# breakout_022218.net
KiCad netlist of a schematic drawn in EAGLE
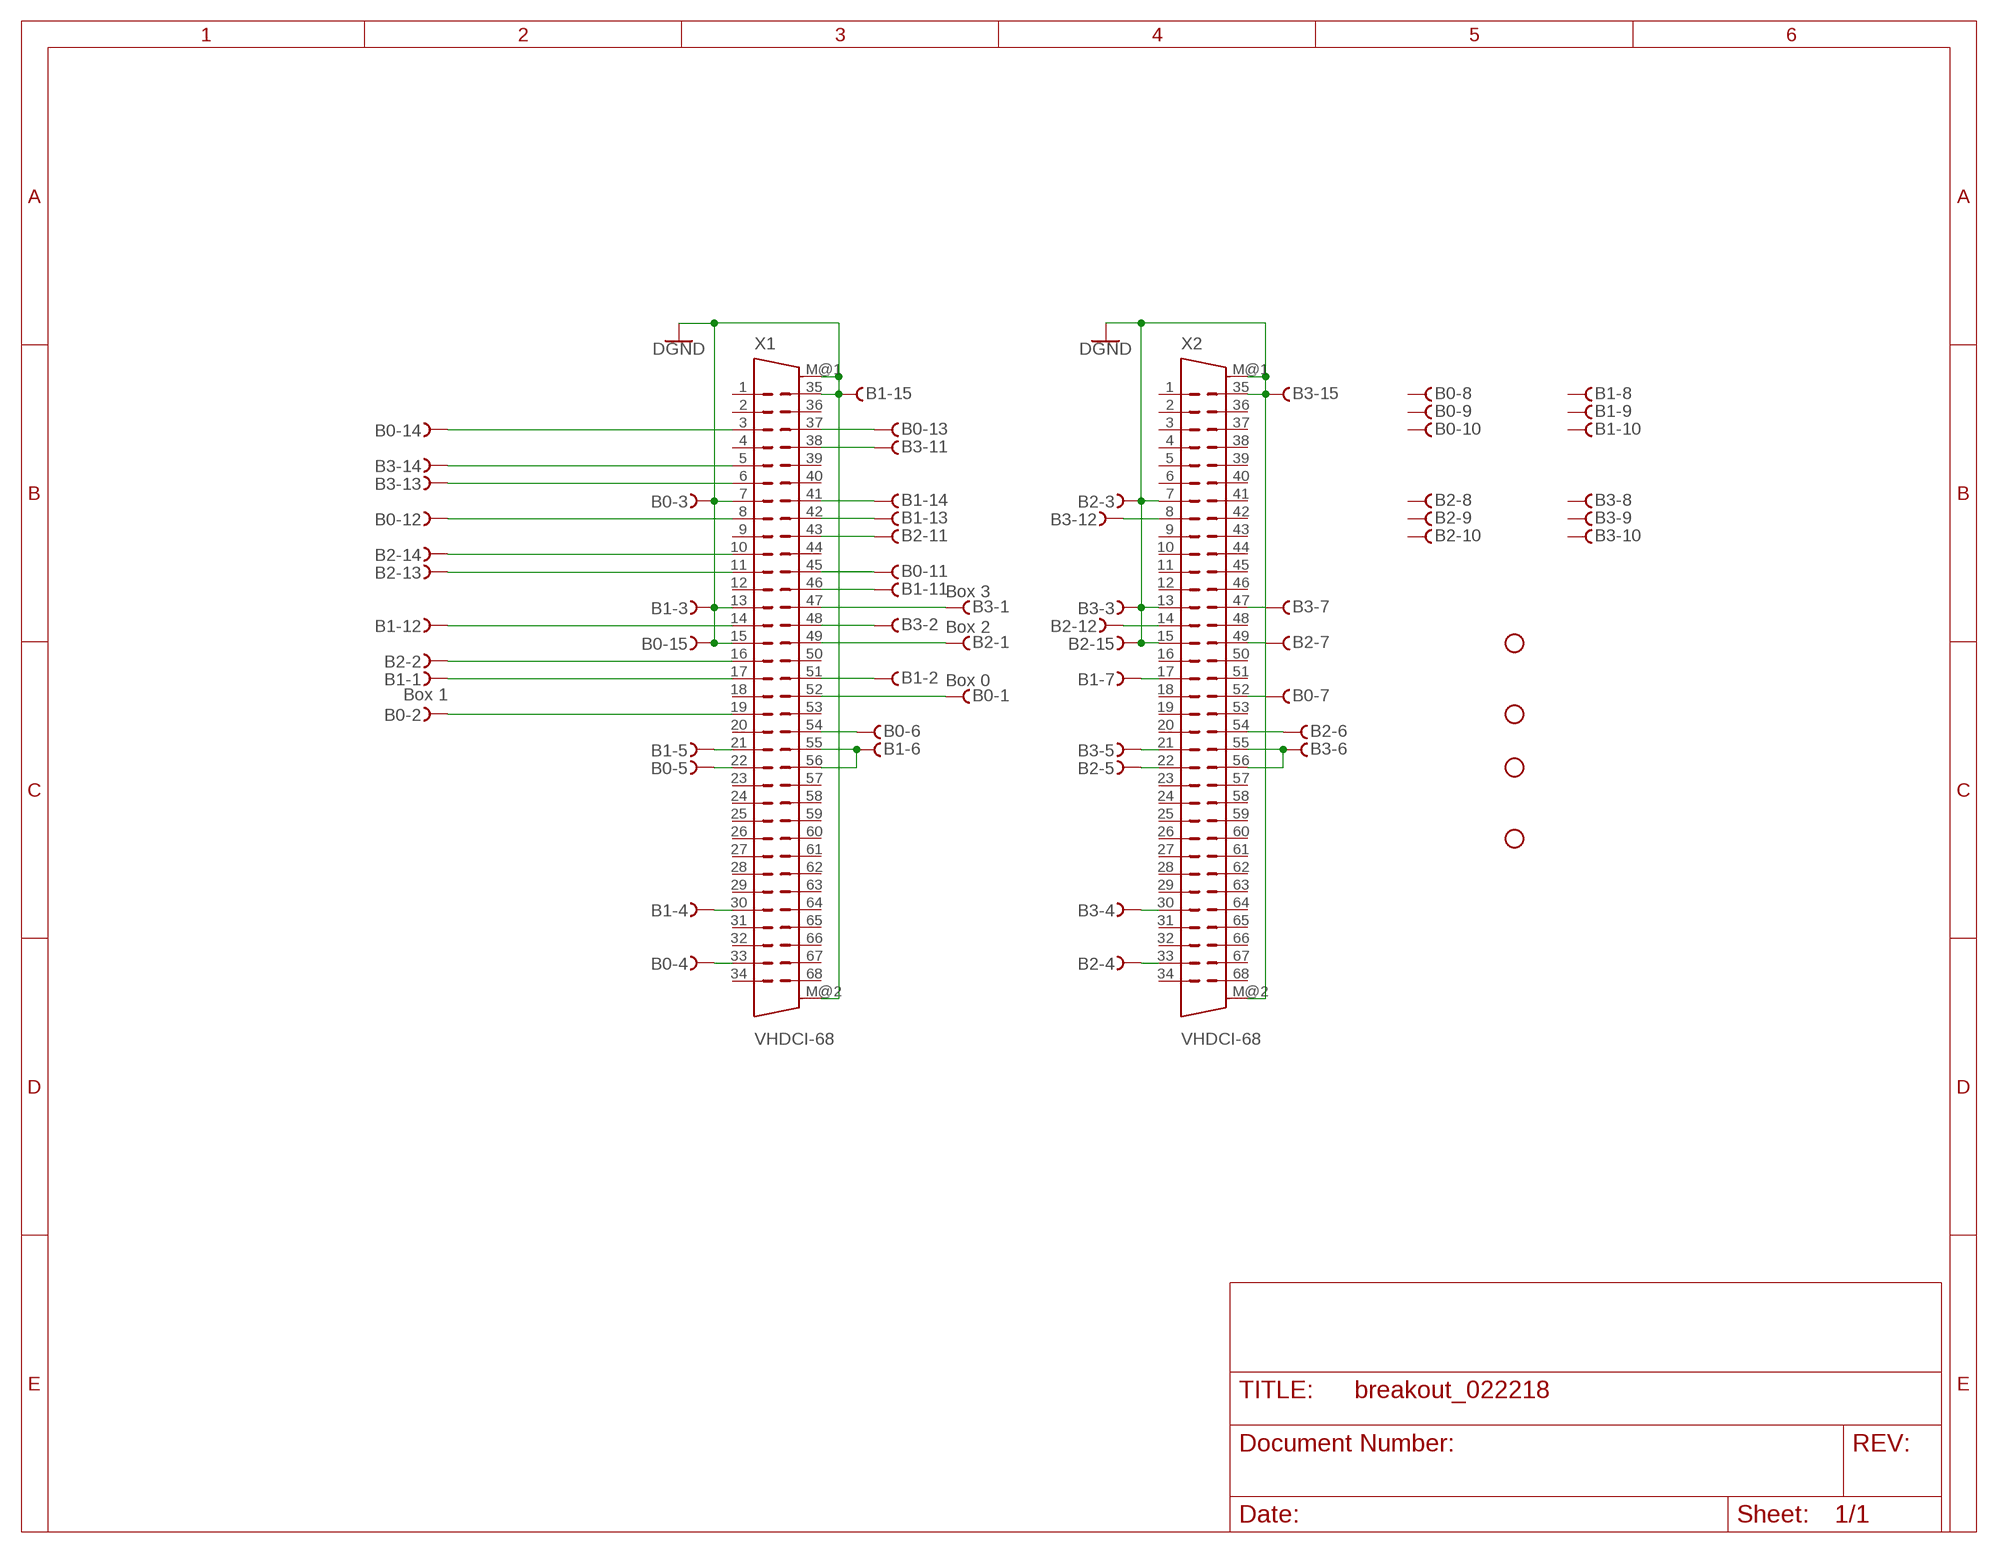
[diagram p0: schematic, sheet 1]

(export (version "E")
  (design (tool "Eeschema 10.0.6"))
  (components
    (comp (ref "B0")
      (value "Box 0")
      (footprint "eagle-import:HDR15RA")
      (libsource (lib "eagle-import") (part "D-SUB15-HDR15RA"))
    )
    (comp (ref "B1")
      (value "Box 1")
      (footprint "eagle-import:HDR15RA")
      (libsource (lib "eagle-import") (part "D-SUB15-HDR15RA"))
    )
    (comp (ref "B2")
      (value "Box 2")
      (footprint "eagle-import:HDR15RA")
      (libsource (lib "eagle-import") (part "D-SUB15-HDR15RA"))
    )
    (comp (ref "B3")
      (value "Box 3")
      (footprint "eagle-import:HDR15RA")
      (libsource (lib "eagle-import") (part "D-SUB15-HDR15RA"))
    )
    (comp (ref "H1")
      (value "STAND-OFF")
      (footprint "eagle-import:STAND-OFF")
      (libsource (lib "eagle-import") (part "STAND-OFF"))
    )
    (comp (ref "H2")
      (value "STAND-OFF")
      (footprint "eagle-import:STAND-OFF")
      (libsource (lib "eagle-import") (part "STAND-OFF"))
    )
    (comp (ref "H3")
      (value "STAND-OFF")
      (footprint "eagle-import:STAND-OFF")
      (libsource (lib "eagle-import") (part "STAND-OFF"))
    )
    (comp (ref "H4")
      (value "STAND-OFF")
      (footprint "eagle-import:STAND-OFF")
      (libsource (lib "eagle-import") (part "STAND-OFF"))
    )
    (comp (ref "X1")
      (value "VHDCI-68")
      (footprint "eagle-import:VHDCI-68")
      (fields (field (name "MF") "MOLEX"))
      (libsource (lib "eagle-import") (part "VHDCI-68"))
    )
    (comp (ref "X2")
      (value "VHDCI-68")
      (footprint "eagle-import:VHDCI-68")
      (fields (field (name "MF") "MOLEX"))
      (libsource (lib "eagle-import") (part "VHDCI-68"))
    )
  )
  (nets
    (net (code "1") (name "DGND") (class "Default")
      (node (ref "B0") (pin "15") (pinfunction "F_15") (pintype "passive"))
      (node (ref "B0") (pin "3") (pinfunction "F_3") (pintype "passive"))
      (node (ref "B1") (pin "15") (pinfunction "F_15") (pintype "passive"))
      (node (ref "B1") (pin "3") (pinfunction "F_3") (pintype "passive"))
      (node (ref "B2") (pin "15") (pinfunction "F_15") (pintype "passive"))
      (node (ref "B2") (pin "3") (pinfunction "F_3") (pintype "passive"))
      (node (ref "B3") (pin "15") (pinfunction "F_15") (pintype "passive"))
      (node (ref "B3") (pin "3") (pinfunction "F_3") (pintype "passive"))
      (node (ref "X1") (pin "13") (pinfunction "13_13") (pintype "passive"))
      (node (ref "X1") (pin "15") (pinfunction "15_15") (pintype "passive"))
      (node (ref "X1") (pin "35") (pinfunction "35_35") (pintype "passive"))
      (node (ref "X1") (pin "7") (pinfunction "7_7") (pintype "passive"))
      (node (ref "X1") (pin "M@1") (pinfunction "S_M@1") (pintype "passive"))
      (node (ref "X1") (pin "M@2") (pinfunction "S_M@2") (pintype "passive"))
      (node (ref "X2") (pin "13") (pinfunction "13_13") (pintype "passive"))
      (node (ref "X2") (pin "15") (pinfunction "15_15") (pintype "passive"))
      (node (ref "X2") (pin "35") (pinfunction "35_35") (pintype "passive"))
      (node (ref "X2") (pin "7") (pinfunction "7_7") (pintype "passive"))
      (node (ref "X2") (pin "M@1") (pinfunction "S_M@1") (pintype "passive"))
      (node (ref "X2") (pin "M@2") (pinfunction "S_M@2") (pintype "passive"))
    )
    (net (code "2") (name "Net-(B0A-F)") (class "Default")
      (node (ref "B0") (pin "1") (pinfunction "F_1") (pintype "passive"))
      (node (ref "X1") (pin "52") (pinfunction "52_52") (pintype "passive"))
    )
    (net (code "3") (name "Net-(B0C-F)") (class "Default")
      (node (ref "B0") (pin "11") (pinfunction "F_11") (pintype "passive"))
      (node (ref "X1") (pin "45") (pinfunction "45_45") (pintype "passive"))
    )
    (net (code "4") (name "Net-(B0D-F)") (class "Default")
      (node (ref "B0") (pin "12") (pinfunction "F_12") (pintype "passive"))
      (node (ref "X1") (pin "8") (pinfunction "8_8") (pintype "passive"))
    )
    (net (code "5") (name "Net-(B0E-F)") (class "Default")
      (node (ref "B0") (pin "13") (pinfunction "F_13") (pintype "passive"))
      (node (ref "X1") (pin "37") (pinfunction "37_37") (pintype "passive"))
    )
    (net (code "6") (name "Net-(B0F-F)") (class "Default")
      (node (ref "B0") (pin "14") (pinfunction "F_14") (pintype "passive"))
      (node (ref "X1") (pin "3") (pinfunction "3_3") (pintype "passive"))
    )
    (net (code "7") (name "Net-(B0H-F)") (class "Default")
      (node (ref "B0") (pin "2") (pinfunction "F_2") (pintype "passive"))
      (node (ref "X1") (pin "19") (pinfunction "19_19") (pintype "passive"))
    )
    (net (code "8") (name "Net-(B0J-F)") (class "Default")
      (node (ref "B0") (pin "4") (pinfunction "F_4") (pintype "passive"))
      (node (ref "X1") (pin "33") (pinfunction "33_33") (pintype "passive"))
    )
    (net (code "9") (name "Net-(B0K-F)") (class "Default")
      (node (ref "B0") (pin "5") (pinfunction "F_5") (pintype "passive"))
      (node (ref "X1") (pin "22") (pinfunction "22_22") (pintype "passive"))
    )
    (net (code "10") (name "Net-(B0L-F)") (class "Default")
      (node (ref "B0") (pin "6") (pinfunction "F_6") (pintype "passive"))
      (node (ref "X1") (pin "54") (pinfunction "54_54") (pintype "passive"))
    )
    (net (code "11") (name "Net-(B0M-F)") (class "Default")
      (node (ref "B0") (pin "7") (pinfunction "F_7") (pintype "passive"))
      (node (ref "X2") (pin "52") (pinfunction "52_52") (pintype "passive"))
    )
    (net (code "12") (name "Net-(B1A-F)") (class "Default")
      (node (ref "B1") (pin "1") (pinfunction "F_1") (pintype "passive"))
      (node (ref "X1") (pin "17") (pinfunction "17_17") (pintype "passive"))
    )
    (net (code "13") (name "Net-(B1C-F)") (class "Default")
      (node (ref "B1") (pin "11") (pinfunction "F_11") (pintype "passive"))
      (node (ref "X1") (pin "46") (pinfunction "46_46") (pintype "passive"))
    )
    (net (code "14") (name "Net-(B1D-F)") (class "Default")
      (node (ref "B1") (pin "12") (pinfunction "F_12") (pintype "passive"))
      (node (ref "X1") (pin "14") (pinfunction "14_14") (pintype "passive"))
    )
    (net (code "15") (name "Net-(B1E-F)") (class "Default")
      (node (ref "B1") (pin "13") (pinfunction "F_13") (pintype "passive"))
      (node (ref "X1") (pin "42") (pinfunction "42_42") (pintype "passive"))
    )
    (net (code "16") (name "Net-(B1F-F)") (class "Default")
      (node (ref "B1") (pin "14") (pinfunction "F_14") (pintype "passive"))
      (node (ref "X1") (pin "41") (pinfunction "41_41") (pintype "passive"))
    )
    (net (code "17") (name "Net-(B1H-F)") (class "Default")
      (node (ref "B1") (pin "2") (pinfunction "F_2") (pintype "passive"))
      (node (ref "X1") (pin "51") (pinfunction "51_51") (pintype "passive"))
    )
    (net (code "18") (name "Net-(B1J-F)") (class "Default")
      (node (ref "B1") (pin "4") (pinfunction "F_4") (pintype "passive"))
      (node (ref "X1") (pin "30") (pinfunction "30_30") (pintype "passive"))
    )
    (net (code "19") (name "Net-(B1K-F)") (class "Default")
      (node (ref "B1") (pin "5") (pinfunction "F_5") (pintype "passive"))
      (node (ref "X1") (pin "21") (pinfunction "21_21") (pintype "passive"))
    )
    (net (code "20") (name "Net-(B1L-F)") (class "Default")
      (node (ref "B1") (pin "6") (pinfunction "F_6") (pintype "passive"))
      (node (ref "X1") (pin "55") (pinfunction "55_55") (pintype "passive"))
      (node (ref "X1") (pin "56") (pinfunction "56_56") (pintype "passive"))
    )
    (net (code "21") (name "Net-(B1M-F)") (class "Default")
      (node (ref "B1") (pin "7") (pinfunction "F_7") (pintype "passive"))
      (node (ref "X2") (pin "17") (pinfunction "17_17") (pintype "passive"))
    )
    (net (code "22") (name "Net-(B2A-F)") (class "Default")
      (node (ref "B2") (pin "1") (pinfunction "F_1") (pintype "passive"))
      (node (ref "X1") (pin "49") (pinfunction "49_49") (pintype "passive"))
    )
    (net (code "23") (name "Net-(B2C-F)") (class "Default")
      (node (ref "B2") (pin "11") (pinfunction "F_11") (pintype "passive"))
      (node (ref "X1") (pin "43") (pinfunction "43_43") (pintype "passive"))
    )
    (net (code "24") (name "Net-(B2D-F)") (class "Default")
      (node (ref "B2") (pin "12") (pinfunction "F_12") (pintype "passive"))
      (node (ref "X2") (pin "14") (pinfunction "14_14") (pintype "passive"))
    )
    (net (code "25") (name "Net-(B2E-F)") (class "Default")
      (node (ref "B2") (pin "13") (pinfunction "F_13") (pintype "passive"))
      (node (ref "X1") (pin "11") (pinfunction "11_11") (pintype "passive"))
    )
    (net (code "26") (name "Net-(B2F-F)") (class "Default")
      (node (ref "B2") (pin "14") (pinfunction "F_14") (pintype "passive"))
      (node (ref "X1") (pin "10") (pinfunction "10_10") (pintype "passive"))
    )
    (net (code "27") (name "Net-(B2H-F)") (class "Default")
      (node (ref "B2") (pin "2") (pinfunction "F_2") (pintype "passive"))
      (node (ref "X1") (pin "16") (pinfunction "16_16") (pintype "passive"))
    )
    (net (code "28") (name "Net-(B2J-F)") (class "Default")
      (node (ref "B2") (pin "4") (pinfunction "F_4") (pintype "passive"))
      (node (ref "X2") (pin "33") (pinfunction "33_33") (pintype "passive"))
    )
    (net (code "29") (name "Net-(B2K-F)") (class "Default")
      (node (ref "B2") (pin "5") (pinfunction "F_5") (pintype "passive"))
      (node (ref "X2") (pin "22") (pinfunction "22_22") (pintype "passive"))
    )
    (net (code "30") (name "Net-(B2L-F)") (class "Default")
      (node (ref "B2") (pin "6") (pinfunction "F_6") (pintype "passive"))
      (node (ref "X2") (pin "54") (pinfunction "54_54") (pintype "passive"))
    )
    (net (code "31") (name "Net-(B2M-F)") (class "Default")
      (node (ref "B2") (pin "7") (pinfunction "F_7") (pintype "passive"))
      (node (ref "X2") (pin "49") (pinfunction "49_49") (pintype "passive"))
    )
    (net (code "32") (name "Net-(B3A-F)") (class "Default")
      (node (ref "B3") (pin "1") (pinfunction "F_1") (pintype "passive"))
      (node (ref "X1") (pin "47") (pinfunction "47_47") (pintype "passive"))
    )
    (net (code "33") (name "Net-(B3C-F)") (class "Default")
      (node (ref "B3") (pin "11") (pinfunction "F_11") (pintype "passive"))
      (node (ref "X1") (pin "38") (pinfunction "38_38") (pintype "passive"))
    )
    (net (code "34") (name "Net-(B3D-F)") (class "Default")
      (node (ref "B3") (pin "12") (pinfunction "F_12") (pintype "passive"))
      (node (ref "X2") (pin "8") (pinfunction "8_8") (pintype "passive"))
    )
    (net (code "35") (name "Net-(B3E-F)") (class "Default")
      (node (ref "B3") (pin "13") (pinfunction "F_13") (pintype "passive"))
      (node (ref "X1") (pin "6") (pinfunction "6_6") (pintype "passive"))
    )
    (net (code "36") (name "Net-(B3F-F)") (class "Default")
      (node (ref "B3") (pin "14") (pinfunction "F_14") (pintype "passive"))
      (node (ref "X1") (pin "5") (pinfunction "5_5") (pintype "passive"))
    )
    (net (code "37") (name "Net-(B3H-F)") (class "Default")
      (node (ref "B3") (pin "2") (pinfunction "F_2") (pintype "passive"))
      (node (ref "X1") (pin "48") (pinfunction "48_48") (pintype "passive"))
    )
    (net (code "38") (name "Net-(B3J-F)") (class "Default")
      (node (ref "B3") (pin "4") (pinfunction "F_4") (pintype "passive"))
      (node (ref "X2") (pin "30") (pinfunction "30_30") (pintype "passive"))
    )
    (net (code "39") (name "Net-(B3K-F)") (class "Default")
      (node (ref "B3") (pin "5") (pinfunction "F_5") (pintype "passive"))
      (node (ref "X2") (pin "21") (pinfunction "21_21") (pintype "passive"))
    )
    (net (code "40") (name "Net-(B3L-F)") (class "Default")
      (node (ref "B3") (pin "6") (pinfunction "F_6") (pintype "passive"))
      (node (ref "X2") (pin "55") (pinfunction "55_55") (pintype "passive"))
      (node (ref "X2") (pin "56") (pinfunction "56_56") (pintype "passive"))
    )
    (net (code "41") (name "Net-(B3M-F)") (class "Default")
      (node (ref "B3") (pin "7") (pinfunction "F_7") (pintype "passive"))
      (node (ref "X2") (pin "47") (pinfunction "47_47") (pintype "passive"))
    )
    (net (code "42") (name "unconnected-(B0B-F-Pad10)") (class "Default")
      (node (ref "B0") (pin "10") (pinfunction "F_10") (pintype "passive"))
    )
    (net (code "43") (name "unconnected-(B0N-F-Pad8)") (class "Default")
      (node (ref "B0") (pin "8") (pinfunction "F_8") (pintype "passive"))
    )
    (net (code "44") (name "unconnected-(B0O-F-Pad9)") (class "Default")
      (node (ref "B0") (pin "9") (pinfunction "F_9") (pintype "passive"))
    )
    (net (code "45") (name "unconnected-(B1B-F-Pad10)") (class "Default")
      (node (ref "B1") (pin "10") (pinfunction "F_10") (pintype "passive"))
    )
    (net (code "46") (name "unconnected-(B1N-F-Pad8)") (class "Default")
      (node (ref "B1") (pin "8") (pinfunction "F_8") (pintype "passive"))
    )
    (net (code "47") (name "unconnected-(B1O-F-Pad9)") (class "Default")
      (node (ref "B1") (pin "9") (pinfunction "F_9") (pintype "passive"))
    )
    (net (code "48") (name "unconnected-(B2B-F-Pad10)") (class "Default")
      (node (ref "B2") (pin "10") (pinfunction "F_10") (pintype "passive"))
    )
    (net (code "49") (name "unconnected-(B2N-F-Pad8)") (class "Default")
      (node (ref "B2") (pin "8") (pinfunction "F_8") (pintype "passive"))
    )
    (net (code "50") (name "unconnected-(B2O-F-Pad9)") (class "Default")
      (node (ref "B2") (pin "9") (pinfunction "F_9") (pintype "passive"))
    )
    (net (code "51") (name "unconnected-(B3B-F-Pad10)") (class "Default")
      (node (ref "B3") (pin "10") (pinfunction "F_10") (pintype "passive"))
    )
    (net (code "52") (name "unconnected-(B3N-F-Pad8)") (class "Default")
      (node (ref "B3") (pin "8") (pinfunction "F_8") (pintype "passive"))
    )
    (net (code "53") (name "unconnected-(B3O-F-Pad9)") (class "Default")
      (node (ref "B3") (pin "9") (pinfunction "F_9") (pintype "passive"))
    )
    (net (code "54") (name "unconnected-(X1-Pad1)") (class "Default")
      (node (ref "X1") (pin "1") (pinfunction "1_1") (pintype "passive"))
    )
    (net (code "55") (name "unconnected-(X1-Pad2)") (class "Default")
      (node (ref "X1") (pin "2") (pinfunction "2_2") (pintype "passive"))
    )
    (net (code "56") (name "unconnected-(X1-Pad4)") (class "Default")
      (node (ref "X1") (pin "4") (pinfunction "4_4") (pintype "passive"))
    )
    (net (code "57") (name "unconnected-(X1-Pad9)") (class "Default")
      (node (ref "X1") (pin "9") (pinfunction "9_9") (pintype "passive"))
    )
    (net (code "58") (name "unconnected-(X1-Pad12)") (class "Default")
      (node (ref "X1") (pin "12") (pinfunction "12_12") (pintype "passive"))
    )
    (net (code "59") (name "unconnected-(X1-Pad18)") (class "Default")
      (node (ref "X1") (pin "18") (pinfunction "18_18") (pintype "passive"))
    )
    (net (code "60") (name "unconnected-(X1-Pad20)") (class "Default")
      (node (ref "X1") (pin "20") (pinfunction "20_20") (pintype "passive"))
    )
    (net (code "61") (name "unconnected-(X1-Pad23)") (class "Default")
      (node (ref "X1") (pin "23") (pinfunction "23_23") (pintype "passive"))
    )
    (net (code "62") (name "unconnected-(X1-Pad24)") (class "Default")
      (node (ref "X1") (pin "24") (pinfunction "24_24") (pintype "passive"))
    )
    (net (code "63") (name "unconnected-(X1-Pad25)") (class "Default")
      (node (ref "X1") (pin "25") (pinfunction "25_25") (pintype "passive"))
    )
    (net (code "64") (name "unconnected-(X1-Pad26)") (class "Default")
      (node (ref "X1") (pin "26") (pinfunction "26_26") (pintype "passive"))
    )
    (net (code "65") (name "unconnected-(X1-Pad27)") (class "Default")
      (node (ref "X1") (pin "27") (pinfunction "27_27") (pintype "passive"))
    )
    (net (code "66") (name "unconnected-(X1-Pad28)") (class "Default")
      (node (ref "X1") (pin "28") (pinfunction "28_28") (pintype "passive"))
    )
    (net (code "67") (name "unconnected-(X1-Pad29)") (class "Default")
      (node (ref "X1") (pin "29") (pinfunction "29_29") (pintype "passive"))
    )
    (net (code "68") (name "unconnected-(X1-Pad31)") (class "Default")
      (node (ref "X1") (pin "31") (pinfunction "31_31") (pintype "passive"))
    )
    (net (code "69") (name "unconnected-(X1-Pad32)") (class "Default")
      (node (ref "X1") (pin "32") (pinfunction "32_32") (pintype "passive"))
    )
    (net (code "70") (name "unconnected-(X1-Pad34)") (class "Default")
      (node (ref "X1") (pin "34") (pinfunction "34_34") (pintype "passive"))
    )
    (net (code "71") (name "unconnected-(X1-Pad36)") (class "Default")
      (node (ref "X1") (pin "36") (pinfunction "36_36") (pintype "passive"))
    )
    (net (code "72") (name "unconnected-(X1-Pad39)") (class "Default")
      (node (ref "X1") (pin "39") (pinfunction "39_39") (pintype "passive"))
    )
    (net (code "73") (name "unconnected-(X1-Pad40)") (class "Default")
      (node (ref "X1") (pin "40") (pinfunction "40_40") (pintype "passive"))
    )
    (net (code "74") (name "unconnected-(X1-Pad44)") (class "Default")
      (node (ref "X1") (pin "44") (pinfunction "44_44") (pintype "passive"))
    )
    (net (code "75") (name "unconnected-(X1-Pad50)") (class "Default")
      (node (ref "X1") (pin "50") (pinfunction "50_50") (pintype "passive"))
    )
    (net (code "76") (name "unconnected-(X1-Pad53)") (class "Default")
      (node (ref "X1") (pin "53") (pinfunction "53_53") (pintype "passive"))
    )
    (net (code "77") (name "unconnected-(X1-Pad57)") (class "Default")
      (node (ref "X1") (pin "57") (pinfunction "57_57") (pintype "passive"))
    )
    (net (code "78") (name "unconnected-(X1-Pad58)") (class "Default")
      (node (ref "X1") (pin "58") (pinfunction "58_58") (pintype "passive"))
    )
    (net (code "79") (name "unconnected-(X1-Pad59)") (class "Default")
      (node (ref "X1") (pin "59") (pinfunction "59_59") (pintype "passive"))
    )
    (net (code "80") (name "unconnected-(X1-Pad60)") (class "Default")
      (node (ref "X1") (pin "60") (pinfunction "60_60") (pintype "passive"))
    )
    (net (code "81") (name "unconnected-(X1-Pad61)") (class "Default")
      (node (ref "X1") (pin "61") (pinfunction "61_61") (pintype "passive"))
    )
    (net (code "82") (name "unconnected-(X1-Pad62)") (class "Default")
      (node (ref "X1") (pin "62") (pinfunction "62_62") (pintype "passive"))
    )
    (net (code "83") (name "unconnected-(X1-Pad63)") (class "Default")
      (node (ref "X1") (pin "63") (pinfunction "63_63") (pintype "passive"))
    )
    (net (code "84") (name "unconnected-(X1-Pad64)") (class "Default")
      (node (ref "X1") (pin "64") (pinfunction "64_64") (pintype "passive"))
    )
    (net (code "85") (name "unconnected-(X1-Pad65)") (class "Default")
      (node (ref "X1") (pin "65") (pinfunction "65_65") (pintype "passive"))
    )
    (net (code "86") (name "unconnected-(X1-Pad66)") (class "Default")
      (node (ref "X1") (pin "66") (pinfunction "66_66") (pintype "passive"))
    )
    (net (code "87") (name "unconnected-(X1-Pad67)") (class "Default")
      (node (ref "X1") (pin "67") (pinfunction "67_67") (pintype "passive"))
    )
    (net (code "88") (name "unconnected-(X1-Pad68)") (class "Default")
      (node (ref "X1") (pin "68") (pinfunction "68_68") (pintype "passive"))
    )
    (net (code "89") (name "unconnected-(X2-Pad1)") (class "Default")
      (node (ref "X2") (pin "1") (pinfunction "1_1") (pintype "passive"))
    )
    (net (code "90") (name "unconnected-(X2-Pad2)") (class "Default")
      (node (ref "X2") (pin "2") (pinfunction "2_2") (pintype "passive"))
    )
    (net (code "91") (name "unconnected-(X2-Pad3)") (class "Default")
      (node (ref "X2") (pin "3") (pinfunction "3_3") (pintype "passive"))
    )
    (net (code "92") (name "unconnected-(X2-Pad4)") (class "Default")
      (node (ref "X2") (pin "4") (pinfunction "4_4") (pintype "passive"))
    )
    (net (code "93") (name "unconnected-(X2-Pad5)") (class "Default")
      (node (ref "X2") (pin "5") (pinfunction "5_5") (pintype "passive"))
    )
    (net (code "94") (name "unconnected-(X2-Pad6)") (class "Default")
      (node (ref "X2") (pin "6") (pinfunction "6_6") (pintype "passive"))
    )
    (net (code "95") (name "unconnected-(X2-Pad9)") (class "Default")
      (node (ref "X2") (pin "9") (pinfunction "9_9") (pintype "passive"))
    )
    (net (code "96") (name "unconnected-(X2-Pad10)") (class "Default")
      (node (ref "X2") (pin "10") (pinfunction "10_10") (pintype "passive"))
    )
    (net (code "97") (name "unconnected-(X2-Pad11)") (class "Default")
      (node (ref "X2") (pin "11") (pinfunction "11_11") (pintype "passive"))
    )
    (net (code "98") (name "unconnected-(X2-Pad12)") (class "Default")
      (node (ref "X2") (pin "12") (pinfunction "12_12") (pintype "passive"))
    )
    (net (code "99") (name "unconnected-(X2-Pad16)") (class "Default")
      (node (ref "X2") (pin "16") (pinfunction "16_16") (pintype "passive"))
    )
    (net (code "100") (name "unconnected-(X2-Pad18)") (class "Default")
      (node (ref "X2") (pin "18") (pinfunction "18_18") (pintype "passive"))
    )
    (net (code "101") (name "unconnected-(X2-Pad19)") (class "Default")
      (node (ref "X2") (pin "19") (pinfunction "19_19") (pintype "passive"))
    )
    (net (code "102") (name "unconnected-(X2-Pad20)") (class "Default")
      (node (ref "X2") (pin "20") (pinfunction "20_20") (pintype "passive"))
    )
    (net (code "103") (name "unconnected-(X2-Pad23)") (class "Default")
      (node (ref "X2") (pin "23") (pinfunction "23_23") (pintype "passive"))
    )
    (net (code "104") (name "unconnected-(X2-Pad24)") (class "Default")
      (node (ref "X2") (pin "24") (pinfunction "24_24") (pintype "passive"))
    )
    (net (code "105") (name "unconnected-(X2-Pad25)") (class "Default")
      (node (ref "X2") (pin "25") (pinfunction "25_25") (pintype "passive"))
    )
    (net (code "106") (name "unconnected-(X2-Pad26)") (class "Default")
      (node (ref "X2") (pin "26") (pinfunction "26_26") (pintype "passive"))
    )
    (net (code "107") (name "unconnected-(X2-Pad27)") (class "Default")
      (node (ref "X2") (pin "27") (pinfunction "27_27") (pintype "passive"))
    )
    (net (code "108") (name "unconnected-(X2-Pad28)") (class "Default")
      (node (ref "X2") (pin "28") (pinfunction "28_28") (pintype "passive"))
    )
    (net (code "109") (name "unconnected-(X2-Pad29)") (class "Default")
      (node (ref "X2") (pin "29") (pinfunction "29_29") (pintype "passive"))
    )
    (net (code "110") (name "unconnected-(X2-Pad31)") (class "Default")
      (node (ref "X2") (pin "31") (pinfunction "31_31") (pintype "passive"))
    )
    (net (code "111") (name "unconnected-(X2-Pad32)") (class "Default")
      (node (ref "X2") (pin "32") (pinfunction "32_32") (pintype "passive"))
    )
    (net (code "112") (name "unconnected-(X2-Pad34)") (class "Default")
      (node (ref "X2") (pin "34") (pinfunction "34_34") (pintype "passive"))
    )
    (net (code "113") (name "unconnected-(X2-Pad36)") (class "Default")
      (node (ref "X2") (pin "36") (pinfunction "36_36") (pintype "passive"))
    )
    (net (code "114") (name "unconnected-(X2-Pad37)") (class "Default")
      (node (ref "X2") (pin "37") (pinfunction "37_37") (pintype "passive"))
    )
    (net (code "115") (name "unconnected-(X2-Pad38)") (class "Default")
      (node (ref "X2") (pin "38") (pinfunction "38_38") (pintype "passive"))
    )
    (net (code "116") (name "unconnected-(X2-Pad39)") (class "Default")
      (node (ref "X2") (pin "39") (pinfunction "39_39") (pintype "passive"))
    )
    (net (code "117") (name "unconnected-(X2-Pad40)") (class "Default")
      (node (ref "X2") (pin "40") (pinfunction "40_40") (pintype "passive"))
    )
    (net (code "118") (name "unconnected-(X2-Pad41)") (class "Default")
      (node (ref "X2") (pin "41") (pinfunction "41_41") (pintype "passive"))
    )
    (net (code "119") (name "unconnected-(X2-Pad42)") (class "Default")
      (node (ref "X2") (pin "42") (pinfunction "42_42") (pintype "passive"))
    )
    (net (code "120") (name "unconnected-(X2-Pad43)") (class "Default")
      (node (ref "X2") (pin "43") (pinfunction "43_43") (pintype "passive"))
    )
    (net (code "121") (name "unconnected-(X2-Pad44)") (class "Default")
      (node (ref "X2") (pin "44") (pinfunction "44_44") (pintype "passive"))
    )
    (net (code "122") (name "unconnected-(X2-Pad45)") (class "Default")
      (node (ref "X2") (pin "45") (pinfunction "45_45") (pintype "passive"))
    )
    (net (code "123") (name "unconnected-(X2-Pad46)") (class "Default")
      (node (ref "X2") (pin "46") (pinfunction "46_46") (pintype "passive"))
    )
    (net (code "124") (name "unconnected-(X2-Pad48)") (class "Default")
      (node (ref "X2") (pin "48") (pinfunction "48_48") (pintype "passive"))
    )
    (net (code "125") (name "unconnected-(X2-Pad50)") (class "Default")
      (node (ref "X2") (pin "50") (pinfunction "50_50") (pintype "passive"))
    )
    (net (code "126") (name "unconnected-(X2-Pad51)") (class "Default")
      (node (ref "X2") (pin "51") (pinfunction "51_51") (pintype "passive"))
    )
    (net (code "127") (name "unconnected-(X2-Pad53)") (class "Default")
      (node (ref "X2") (pin "53") (pinfunction "53_53") (pintype "passive"))
    )
    (net (code "128") (name "unconnected-(X2-Pad57)") (class "Default")
      (node (ref "X2") (pin "57") (pinfunction "57_57") (pintype "passive"))
    )
    (net (code "129") (name "unconnected-(X2-Pad58)") (class "Default")
      (node (ref "X2") (pin "58") (pinfunction "58_58") (pintype "passive"))
    )
    (net (code "130") (name "unconnected-(X2-Pad59)") (class "Default")
      (node (ref "X2") (pin "59") (pinfunction "59_59") (pintype "passive"))
    )
    (net (code "131") (name "unconnected-(X2-Pad60)") (class "Default")
      (node (ref "X2") (pin "60") (pinfunction "60_60") (pintype "passive"))
    )
    (net (code "132") (name "unconnected-(X2-Pad61)") (class "Default")
      (node (ref "X2") (pin "61") (pinfunction "61_61") (pintype "passive"))
    )
    (net (code "133") (name "unconnected-(X2-Pad62)") (class "Default")
      (node (ref "X2") (pin "62") (pinfunction "62_62") (pintype "passive"))
    )
    (net (code "134") (name "unconnected-(X2-Pad63)") (class "Default")
      (node (ref "X2") (pin "63") (pinfunction "63_63") (pintype "passive"))
    )
    (net (code "135") (name "unconnected-(X2-Pad64)") (class "Default")
      (node (ref "X2") (pin "64") (pinfunction "64_64") (pintype "passive"))
    )
    (net (code "136") (name "unconnected-(X2-Pad65)") (class "Default")
      (node (ref "X2") (pin "65") (pinfunction "65_65") (pintype "passive"))
    )
    (net (code "137") (name "unconnected-(X2-Pad66)") (class "Default")
      (node (ref "X2") (pin "66") (pinfunction "66_66") (pintype "passive"))
    )
    (net (code "138") (name "unconnected-(X2-Pad67)") (class "Default")
      (node (ref "X2") (pin "67") (pinfunction "67_67") (pintype "passive"))
    )
    (net (code "139") (name "unconnected-(X2-Pad68)") (class "Default")
      (node (ref "X2") (pin "68") (pinfunction "68_68") (pintype "passive"))
    )
  )
)
